# CET_GPS_5_03_22_new_route.net
KiCad netlist of a schematic drawn in EAGLE
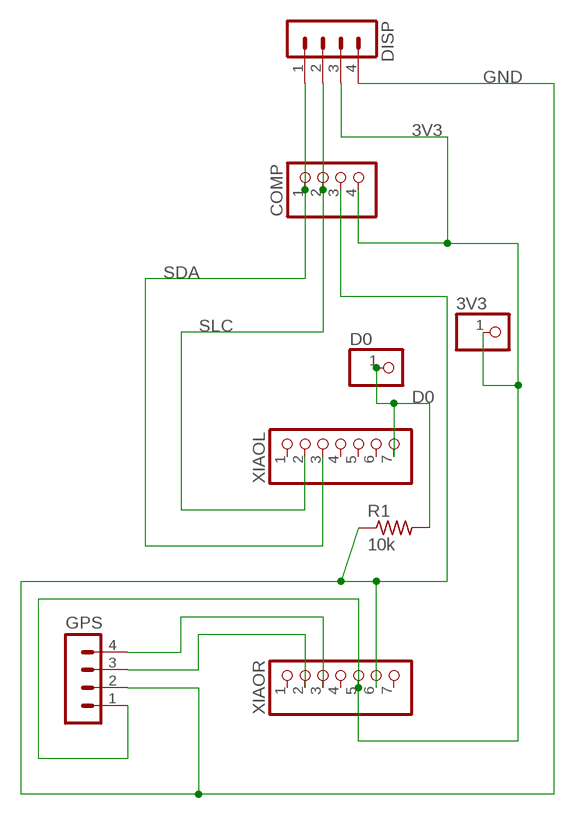
[diagram p0: schematic, sheet 1]

(export (version "E")
  (design (tool "Eeschema 10.0.6"))
  (components
    (comp (ref "3V3")
      (value "PINHD-1X1")
      (footprint "eagle-import:1X01")
      (libsource (lib "eagle-import") (part "PINHD-1X1"))
    )
    (comp (ref "COMP")
      (value "PINHD-1X4/90")
      (footprint "eagle-import:1X04_90")
      (libsource (lib "eagle-import") (part "PINHD-1X4/90"))
    )
    (comp (ref "D0")
      (value "PINHD-1X1")
      (footprint "eagle-import:1X01")
      (libsource (lib "eagle-import") (part "PINHD-1X1"))
    )
    (comp (ref "DISP")
      (value "MA04-1")
      (footprint "eagle-import:MA04-1")
      (libsource (lib "eagle-import") (part "MA04-1"))
    )
    (comp (ref "GPS")
      (value "MA04-1")
      (footprint "eagle-import:MA04-1")
      (libsource (lib "eagle-import") (part "MA04-1"))
    )
    (comp (ref "R1")
      (value "10k")
      (footprint "eagle-import:0204_7")
      (libsource (lib "eagle-import") (part "R-US_0204/7"))
    )
    (comp (ref "XIAOL")
      (value "PINHD-1X7")
      (footprint "eagle-import:1X07")
      (libsource (lib "eagle-import") (part "PINHD-1X7"))
    )
    (comp (ref "XIAOR")
      (value "PINHD-1X7")
      (footprint "eagle-import:1X07")
      (libsource (lib "eagle-import") (part "PINHD-1X7"))
    )
  )
  (nets
    (net (code "1") (name "/3V3") (class "Default")
      (node (ref "3V3") (pin "1") (pinfunction "1_1") (pintype "passive"))
      (node (ref "COMP") (pin "4") (pinfunction "4_4") (pintype "passive"))
      (node (ref "DISP") (pin "3") (pinfunction "3_3") (pintype "passive"))
      (node (ref "GPS") (pin "1") (pinfunction "1_1") (pintype "passive"))
      (node (ref "XIAOR") (pin "5") (pinfunction "5_5") (pintype "passive"))
    )
    (net (code "2") (name "/D0") (class "Default")
      (node (ref "D0") (pin "1") (pinfunction "1_1") (pintype "passive"))
      (node (ref "R1") (pin "2") (pinfunction "2_2") (pintype "passive"))
      (node (ref "XIAOL") (pin "7") (pinfunction "7_7") (pintype "passive"))
    )
    (net (code "3") (name "/GND") (class "Default")
      (node (ref "COMP") (pin "3") (pinfunction "3_3") (pintype "passive"))
      (node (ref "DISP") (pin "4") (pinfunction "4_4") (pintype "passive"))
      (node (ref "GPS") (pin "2") (pinfunction "2_2") (pintype "passive"))
      (node (ref "R1") (pin "1") (pinfunction "1_1") (pintype "passive"))
      (node (ref "XIAOR") (pin "6") (pinfunction "6_6") (pintype "passive"))
    )
    (net (code "4") (name "/SDA") (class "Default")
      (node (ref "COMP") (pin "1") (pinfunction "1_1") (pintype "passive"))
      (node (ref "DISP") (pin "1") (pinfunction "1_1") (pintype "passive"))
      (node (ref "XIAOL") (pin "3") (pinfunction "3_3") (pintype "passive"))
    )
    (net (code "5") (name "/SLC") (class "Default")
      (node (ref "COMP") (pin "2") (pinfunction "2_2") (pintype "passive"))
      (node (ref "DISP") (pin "2") (pinfunction "2_2") (pintype "passive"))
      (node (ref "XIAOL") (pin "2") (pinfunction "2_2") (pintype "passive"))
    )
    (net (code "6") (name "Net-(GPS-Pad3)") (class "Default")
      (node (ref "GPS") (pin "3") (pinfunction "3_3") (pintype "passive"))
      (node (ref "XIAOR") (pin "2") (pinfunction "2_2") (pintype "passive"))
    )
    (net (code "7") (name "Net-(GPS-Pad4)") (class "Default")
      (node (ref "GPS") (pin "4") (pinfunction "4_4") (pintype "passive"))
      (node (ref "XIAOR") (pin "3") (pinfunction "3_3") (pintype "passive"))
    )
    (net (code "8") (name "unconnected-(XIAOL-Pad1)") (class "Default")
      (node (ref "XIAOL") (pin "1") (pinfunction "1_1") (pintype "passive"))
    )
    (net (code "9") (name "unconnected-(XIAOL-Pad4)") (class "Default")
      (node (ref "XIAOL") (pin "4") (pinfunction "4_4") (pintype "passive"))
    )
    (net (code "10") (name "unconnected-(XIAOL-Pad5)") (class "Default")
      (node (ref "XIAOL") (pin "5") (pinfunction "5_5") (pintype "passive"))
    )
    (net (code "11") (name "unconnected-(XIAOL-Pad6)") (class "Default")
      (node (ref "XIAOL") (pin "6") (pinfunction "6_6") (pintype "passive"))
    )
    (net (code "12") (name "unconnected-(XIAOR-Pad1)") (class "Default")
      (node (ref "XIAOR") (pin "1") (pinfunction "1_1") (pintype "passive"))
    )
    (net (code "13") (name "unconnected-(XIAOR-Pad4)") (class "Default")
      (node (ref "XIAOR") (pin "4") (pinfunction "4_4") (pintype "passive"))
    )
    (net (code "14") (name "unconnected-(XIAOR-Pad7)") (class "Default")
      (node (ref "XIAOR") (pin "7") (pinfunction "7_7") (pintype "passive"))
    )
  )
)
